# SmartSwitchV3.net
KiCad netlist of a schematic drawn in Altium Designer
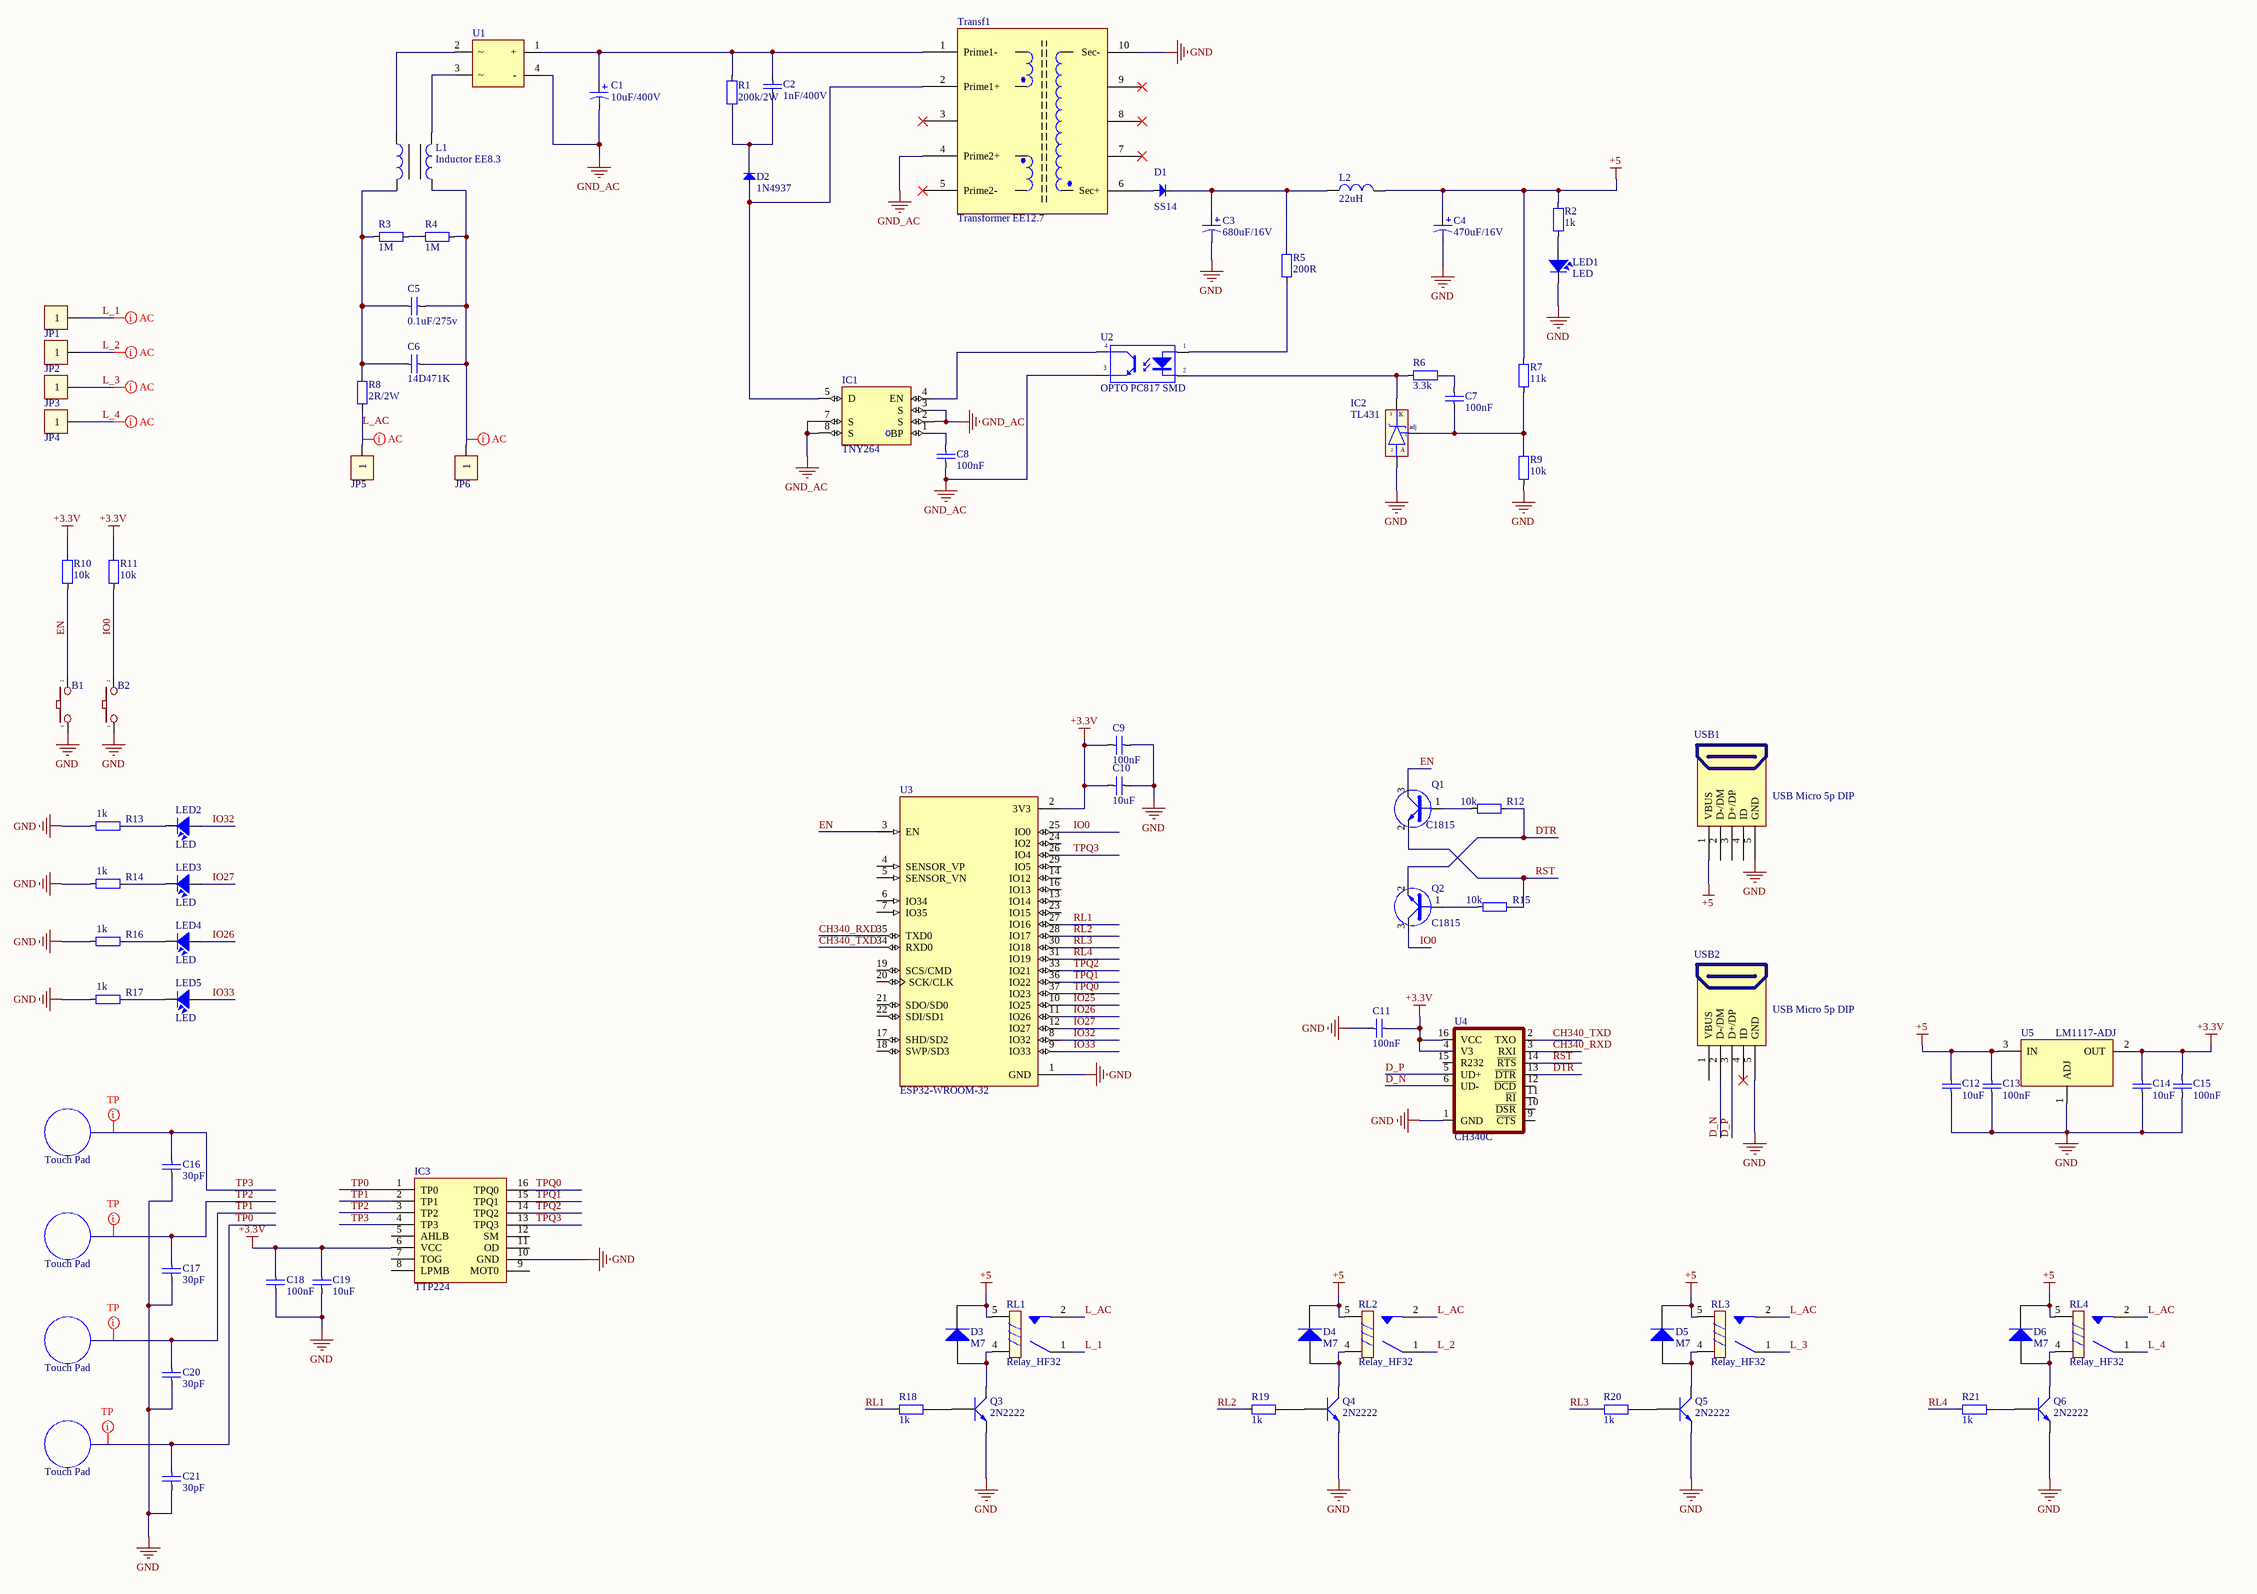
[diagram p0: SmartSwitchV3.SchDoc]

(export (version "E")
  (design (tool "Eeschema 10.0.6"))
  (components
    (comp (ref "B1")
      (value "Button 3x4x2.5")
      (footprint "Button 3x4x2.5")
      (libsource (lib "My Library") (part "Button 3x4x2.5"))
    )
    (comp (ref "B2")
      (value "Button 3x4x2.5")
      (footprint "Button 3x4x2.5")
      (libsource (lib "My Library") (part "Button 3x4x2.5"))
    )
    (comp (ref "C1")
      (value "10uF/400V")
      (footprint "C10mm")
      (description "Polarized Capacitor (Axial)")
      (fields (field (name "PUBLISHER") "Altium Limited"))
      (libsource (lib "My Library") (part "Cap Pol"))
    )
    (comp (ref "C2")
      (value "1nF/400V")
      (footprint "103/2KV")
      (description "CAP CERAMIC")
      (fields (field (name "PUBLISHER") "Altium Limited"))
      (libsource (lib "My Library") (part "Cap2KV"))
    )
    (comp (ref "C3")
      (value "680uF/16V")
      (footprint "C8mm")
      (description "Polarized Capacitor (Axial)")
      (fields (field (name "PUBLISHER") "Altium Limited"))
      (libsource (lib "My Library") (part "Cap Pol"))
    )
    (comp (ref "C4")
      (value "470uF/16V")
      (footprint "C8mm")
      (description "Polarized Capacitor (Axial)")
      (fields (field (name "PUBLISHER") "Altium Limited"))
      (libsource (lib "My Library") (part "Cap Pol"))
    )
    (comp (ref "C5")
      (value "0.1uF/275v")
      (footprint "Cap AC filter")
      (description "Tụ lọc nguồn AC 0.1uf 275v 10mm")
      (libsource (lib "My Library") (part "Cap AC filter"))
    )
    (comp (ref "C6")
      (value "14D471K")
      (footprint "103/2KV")
      (description "Capacitor Ceramic 2KV")
      (fields (field (name "PUBLISHER") "Altium Limited"))
      (libsource (lib "My Library") (part "Cap2KV"))
    )
    (comp (ref "C7")
      (value "100nF")
      (footprint "CAP_0805")
      (description "Capacitor")
      (fields (field (name "PUBLISHER") "Altium Limited"))
      (libsource (lib "My Library") (part "CapSMD"))
    )
    (comp (ref "C8")
      (value "100nF")
      (footprint "CAP_0805")
      (description "Capacitor")
      (fields (field (name "PUBLISHER") "Altium Limited"))
      (libsource (lib "My Library") (part "CapSMD"))
    )
    (comp (ref "C9")
      (value "100nF")
      (footprint "CAP_0805")
      (description "Capacitor")
      (fields (field (name "PUBLISHER") "Altium Limited"))
      (libsource (lib "My Library") (part "CapSMD"))
    )
    (comp (ref "C10")
      (value "10uF")
      (footprint "CAP_0805")
      (description "Capacitor")
      (fields (field (name "PUBLISHER") "Altium Limited"))
      (libsource (lib "My Library") (part "CapSMD"))
    )
    (comp (ref "C11")
      (value "100nF")
      (footprint "CAP_0805")
      (description "Capacitor")
      (fields (field (name "PUBLISHER") "Altium Limited"))
      (libsource (lib "My Library") (part "CapSMD"))
    )
    (comp (ref "C12")
      (value "10uF")
      (footprint "CAP_0805")
      (description "Capacitor")
      (fields (field (name "PUBLISHER") "Altium Limited"))
      (libsource (lib "My Library") (part "CapSMD"))
    )
    (comp (ref "C13")
      (value "100nF")
      (footprint "CAP_0805")
      (description "Capacitor")
      (fields (field (name "PUBLISHER") "Altium Limited"))
      (libsource (lib "My Library") (part "CapSMD"))
    )
    (comp (ref "C14")
      (value "10uF")
      (footprint "CAP_0805")
      (description "Capacitor")
      (fields (field (name "PUBLISHER") "Altium Limited"))
      (libsource (lib "My Library") (part "CapSMD"))
    )
    (comp (ref "C15")
      (value "100nF")
      (footprint "CAP_0805")
      (description "Capacitor")
      (fields (field (name "PUBLISHER") "Altium Limited"))
      (libsource (lib "My Library") (part "CapSMD"))
    )
    (comp (ref "C16")
      (value "30pF")
      (footprint "CAP_0805")
      (description "Capacitor")
      (fields (field (name "PUBLISHER") "Altium Limited"))
      (libsource (lib "My Library") (part "CapSMD"))
    )
    (comp (ref "C17")
      (value "30pF")
      (footprint "CAP_0805")
      (description "Capacitor")
      (fields (field (name "PUBLISHER") "Altium Limited"))
      (libsource (lib "My Library") (part "CapSMD"))
    )
    (comp (ref "C18")
      (value "100nF")
      (footprint "CAP_0805")
      (description "Capacitor")
      (fields (field (name "PUBLISHER") "Altium Limited"))
      (libsource (lib "My Library") (part "CapSMD"))
    )
    (comp (ref "C19")
      (value "10uF")
      (footprint "CAP_0805")
      (description "Capacitor")
      (fields (field (name "PUBLISHER") "Altium Limited"))
      (libsource (lib "My Library") (part "CapSMD"))
    )
    (comp (ref "C20")
      (value "30pF")
      (footprint "CAP_0805")
      (description "Capacitor")
      (fields (field (name "PUBLISHER") "Altium Limited"))
      (libsource (lib "My Library") (part "CapSMD"))
    )
    (comp (ref "C21")
      (value "30pF")
      (footprint "CAP_0805")
      (description "Capacitor")
      (fields (field (name "PUBLISHER") "Altium Limited"))
      (libsource (lib "My Library") (part "CapSMD"))
    )
    (comp (ref "D1")
      (value "SS14")
      (footprint "DO-214AA(SMB)")
      (description "Diode Schottky\r\n1N5819")
      (fields (field (name "PUBLISHER") "Altium Limited"))
      (libsource (lib "My Library") (part "Diode SMD"))
    )
    (comp (ref "D2")
      (value "1N4937")
      (footprint "DIO-1AN")
      (description "Diode Schottky\r\n1N4937")
      (fields (field (name "PUBLISHER") "Altium Limited"))
      (libsource (lib "My Library") (part "Diode SMD"))
    )
    (comp (ref "D3")
      (value "M7")
      (footprint "DIODE SMA")
      (description "Dán")
      (libsource (lib "Altium_Lib_by_KhueNguyenCreator") (part "Diode M7 ( 4007 )"))
    )
    (comp (ref "D4")
      (value "M7")
      (footprint "DIODE SMA")
      (description "Dán")
      (libsource (lib "Altium_Lib_by_KhueNguyenCreator") (part "Diode M7 ( 4007 )"))
    )
    (comp (ref "D5")
      (value "M7")
      (footprint "DIODE SMA")
      (description "Dán")
      (libsource (lib "Altium_Lib_by_KhueNguyenCreator") (part "Diode M7 ( 4007 )"))
    )
    (comp (ref "D6")
      (value "M7")
      (footprint "DIODE SMA")
      (description "Dán")
      (libsource (lib "Altium_Lib_by_KhueNguyenCreator") (part "Diode M7 ( 4007 )"))
    )
    (comp (ref "IC1")
      (value "TNY264")
      (footprint "TNY264")
      (description "IC Power")
      (libsource (lib "My Library") (part "TNY264"))
    )
    (comp (ref "IC2")
      (value "TL431")
      (footprint "qto-92")
      (description "Programmable Shunt Regulator")
      (libsource (lib "My Library") (part "TL431"))
    )
    (comp (ref "IC3") (value "TTP224") (footprint "TTP224") (libsource (lib "My Library") (part "TTP224")))
    (comp (ref "JP1")
      (value "Coc_dong")
      (footprint "Coc_dong")
      (libsource (lib "My Library") (part "Coc_dong"))
    )
    (comp (ref "JP2")
      (value "Coc_dong")
      (footprint "Coc_dong")
      (libsource (lib "My Library") (part "Coc_dong"))
    )
    (comp (ref "JP3")
      (value "Coc_dong")
      (footprint "Coc_dong")
      (libsource (lib "My Library") (part "Coc_dong"))
    )
    (comp (ref "JP4")
      (value "Coc_dong")
      (footprint "Coc_dong")
      (libsource (lib "My Library") (part "Coc_dong"))
    )
    (comp (ref "JP5") (value "Coc_dong") (footprint "Coc_dong") (libsource (lib "") (part "Coc_dong_1")))
    (comp (ref "JP6") (value "Coc_dong") (footprint "Coc_dong") (libsource (lib "") (part "Coc_dong_1")))
    (comp (ref "L1")
      (value "Inductor EE8.3")
      (footprint "Inductor EE8.3")
      (libsource (lib "My Library") (part "Inductor EE8.3"))
    )
    (comp (ref "L2")
      (value "22uH")
      (footprint "L_SMD")
      (description "CD73R 22uH 1.23A 7345")
      (libsource (lib "My Library") (part "Inductor"))
    )
    (comp (ref "LED1")
      (value "LED")
      (footprint "LED-0805-Red")
      (description "LED Single colour Green and Red")
      (libsource (lib "My Library") (part "LED"))
    )
    (comp (ref "LED2")
      (value "LED")
      (footprint "LED-0805-Red")
      (description "LED Single colour Green and Red")
      (libsource (lib "My Library") (part "LED"))
    )
    (comp (ref "LED3")
      (value "LED")
      (footprint "LED-0805-Red")
      (description "LED Single colour Green and Red")
      (libsource (lib "My Library") (part "LED"))
    )
    (comp (ref "LED4")
      (value "LED")
      (footprint "LED-0805-Red")
      (description "LED Single colour Green and Red")
      (libsource (lib "My Library") (part "LED"))
    )
    (comp (ref "LED5")
      (value "LED")
      (footprint "LED-0805-Red")
      (description "LED Single colour Green and Red")
      (libsource (lib "My Library") (part "LED"))
    )
    (comp (ref "Q1")
      (value "C1815")
      (footprint "SOT23D")
      (description "NPN 600mW, ECB")
      (libsource (lib "") (part "2SC1815_1"))
    )
    (comp (ref "Q2")
      (value "C1815")
      (footprint "SOT23D")
      (description "NPN 600mW, ECB")
      (libsource (lib "My Library") (part "2SC1815"))
    )
    (comp (ref "Q3")
      (value "2N2222")
      (footprint "SOT23")
      (description "NPN transistor")
      (libsource (lib "Altium_Lib_by_KhueNguyenCreator") (part "C1815 HF SMD"))
    )
    (comp (ref "Q4")
      (value "2N2222")
      (footprint "SOT23")
      (description "NPN transistor")
      (libsource (lib "Altium_Lib_by_KhueNguyenCreator") (part "C1815 HF SMD"))
    )
    (comp (ref "Q5")
      (value "2N2222")
      (footprint "SOT23")
      (description "NPN transistor")
      (libsource (lib "Altium_Lib_by_KhueNguyenCreator") (part "C1815 HF SMD"))
    )
    (comp (ref "Q6")
      (value "2N2222")
      (footprint "SOT23")
      (description "NPN transistor")
      (libsource (lib "Altium_Lib_by_KhueNguyenCreator") (part "C1815 HF SMD"))
    )
    (comp (ref "R1")
      (value "200k/2W")
      (footprint "RES-1WW")
      (description "Resistor")
      (fields
        (field (name "MANUFACTURER") "Generic Components")
        (field (name "PUBLISHER") "Altium Hobart Technology Centre")
      )
      (libsource (lib "My Library") (part "Resistor - SMD"))
    )
    (comp (ref "R2")
      (value "1k")
      (footprint "RES-SMD-0805")
      (description "Resistor")
      (fields
        (field (name "MANUFACTURER") "Generic Components")
        (field (name "PUBLISHER") "Altium Hobart Technology Centre")
      )
      (libsource (lib "My Library") (part "Resistor - SMD"))
    )
    (comp (ref "R3")
      (value "1M")
      (footprint "RES-SMD-1206")
      (description "Resistor")
      (fields
        (field (name "MANUFACTURER") "Generic Components")
        (field (name "PUBLISHER") "Altium Hobart Technology Centre")
      )
      (libsource (lib "My Library") (part "Resistor - SMD"))
    )
    (comp (ref "R4")
      (value "1M")
      (footprint "RES-SMD-1206")
      (description "Resistor")
      (fields
        (field (name "MANUFACTURER") "Generic Components")
        (field (name "PUBLISHER") "Altium Hobart Technology Centre")
      )
      (libsource (lib "My Library") (part "Resistor - SMD"))
    )
    (comp (ref "R5")
      (value "200R")
      (footprint "RES-SMD-0805")
      (description "Resistor")
      (fields
        (field (name "MANUFACTURER") "Generic Components")
        (field (name "PUBLISHER") "Altium Hobart Technology Centre")
      )
      (libsource (lib "My Library") (part "Resistor - SMD"))
    )
    (comp (ref "R6")
      (value "3.3k")
      (footprint "RES-SMD-0805")
      (description "Resistor")
      (fields
        (field (name "MANUFACTURER") "Generic Components")
        (field (name "PUBLISHER") "Altium Hobart Technology Centre")
      )
      (libsource (lib "My Library") (part "Resistor - SMD"))
    )
    (comp (ref "R7")
      (value "11k")
      (footprint "RES-SMD-0805")
      (description "Resistor")
      (fields
        (field (name "MANUFACTURER") "Generic Components")
        (field (name "PUBLISHER") "Altium Hobart Technology Centre")
      )
      (libsource (lib "My Library") (part "Resistor - SMD"))
    )
    (comp (ref "R8")
      (value "2R/2W")
      (footprint "RES-1WW")
      (description "Resistor")
      (fields
        (field (name "MANUFACTURER") "Generic Components")
        (field (name "PUBLISHER") "Altium Hobart Technology Centre")
      )
      (libsource (lib "My Library") (part "Resistor - SMD"))
    )
    (comp (ref "R9")
      (value "10k")
      (footprint "RES-SMD-0805")
      (description "Resistor")
      (fields
        (field (name "MANUFACTURER") "Generic Components")
        (field (name "PUBLISHER") "Altium Hobart Technology Centre")
      )
      (libsource (lib "My Library") (part "Resistor - SMD"))
    )
    (comp (ref "R10")
      (value "10k")
      (footprint "RES-SMD-0805")
      (description "Resistor")
      (fields
        (field (name "MANUFACTURER") "Generic Components")
        (field (name "PUBLISHER") "Altium Hobart Technology Centre")
      )
      (libsource (lib "My Library") (part "Resistor - SMD"))
    )
    (comp (ref "R11")
      (value "10k")
      (footprint "RES-SMD-0805")
      (description "Resistor")
      (fields
        (field (name "MANUFACTURER") "Generic Components")
        (field (name "PUBLISHER") "Altium Hobart Technology Centre")
      )
      (libsource (lib "My Library") (part "Resistor - SMD"))
    )
    (comp (ref "R12")
      (value "10k")
      (footprint "RES-SMD-0805")
      (description "Resistor")
      (fields
        (field (name "MANUFACTURER") "Generic Components")
        (field (name "PUBLISHER") "Altium Hobart Technology Centre")
      )
      (libsource (lib "My Library") (part "Resistor - SMD"))
    )
    (comp (ref "R13")
      (value "1k")
      (footprint "RES-SMD-0805")
      (description "Resistor")
      (fields
        (field (name "MANUFACTURER") "Generic Components")
        (field (name "PUBLISHER") "Altium Hobart Technology Centre")
      )
      (libsource (lib "My Library") (part "Resistor - SMD"))
    )
    (comp (ref "R14")
      (value "1k")
      (footprint "RES-SMD-0805")
      (description "Resistor")
      (fields
        (field (name "MANUFACTURER") "Generic Components")
        (field (name "PUBLISHER") "Altium Hobart Technology Centre")
      )
      (libsource (lib "My Library") (part "Resistor - SMD"))
    )
    (comp (ref "R15")
      (value "10k")
      (footprint "RES-SMD-0805")
      (description "Resistor")
      (fields
        (field (name "MANUFACTURER") "Generic Components")
        (field (name "PUBLISHER") "Altium Hobart Technology Centre")
      )
      (libsource (lib "My Library") (part "Resistor - SMD"))
    )
    (comp (ref "R16")
      (value "1k")
      (footprint "RES-SMD-0805")
      (description "Resistor")
      (fields
        (field (name "MANUFACTURER") "Generic Components")
        (field (name "PUBLISHER") "Altium Hobart Technology Centre")
      )
      (libsource (lib "My Library") (part "Resistor - SMD"))
    )
    (comp (ref "R17")
      (value "1k")
      (footprint "RES-SMD-0805")
      (description "Resistor")
      (fields
        (field (name "MANUFACTURER") "Generic Components")
        (field (name "PUBLISHER") "Altium Hobart Technology Centre")
      )
      (libsource (lib "My Library") (part "Resistor - SMD"))
    )
    (comp (ref "R18")
      (value "1k")
      (footprint "RES-SMD-0805")
      (description "Resistor")
      (fields
        (field (name "MANUFACTURER") "Generic Components")
        (field (name "PUBLISHER") "Altium Hobart Technology Centre")
      )
      (libsource (lib "My Library") (part "Resistor - SMD"))
    )
    (comp (ref "R19")
      (value "1k")
      (footprint "RES-SMD-0805")
      (description "Resistor")
      (fields
        (field (name "MANUFACTURER") "Generic Components")
        (field (name "PUBLISHER") "Altium Hobart Technology Centre")
      )
      (libsource (lib "My Library") (part "Resistor - SMD"))
    )
    (comp (ref "R20")
      (value "1k")
      (footprint "RES-SMD-0805")
      (description "Resistor")
      (fields
        (field (name "MANUFACTURER") "Generic Components")
        (field (name "PUBLISHER") "Altium Hobart Technology Centre")
      )
      (libsource (lib "My Library") (part "Resistor - SMD"))
    )
    (comp (ref "R21")
      (value "1k")
      (footprint "RES-SMD-0805")
      (description "Resistor")
      (fields
        (field (name "MANUFACTURER") "Generic Components")
        (field (name "PUBLISHER") "Altium Hobart Technology Centre")
      )
      (libsource (lib "My Library") (part "Resistor - SMD"))
    )
    (comp (ref "RL1")
      (value "Relay_HF32")
      (footprint "HF32F")
      (libsource (lib "My Library") (part "Relay_HF32"))
    )
    (comp (ref "RL2")
      (value "Relay_HF32")
      (footprint "HF32F")
      (libsource (lib "My Library") (part "Relay_HF32"))
    )
    (comp (ref "RL3")
      (value "Relay_HF32")
      (footprint "HF32F")
      (libsource (lib "My Library") (part "Relay_HF32"))
    )
    (comp (ref "RL4")
      (value "Relay_HF32")
      (footprint "HF32F")
      (libsource (lib "My Library") (part "Relay_HF32"))
    )
    (comp (ref "Transf1")
      (value "Transformer EE12.7")
      (footprint "Transformer EE12.7")
      (libsource (lib "My Library") (part "Tranformer EE16"))
    )
    (comp (ref "U1")
      (value "Diode Bridge Flate")
      (footprint "DB207S")
      (description "Diode Bridge")
      (libsource (lib "My Library") (part "Diode Bridge Flate"))
    )
    (comp (ref "U2")
      (value "OPTO PC817 SMD")
      (footprint "SOP4")
      (description "Single Opto")
      (libsource (lib "Altium_Lib_by_KhueNguyenCreator") (part "OPTO PC817 SMD"))
    )
    (comp (ref "U3")
      (value "ESP32-WROOM-32")
      (footprint "MODULE_ESP32-WROOM-32")
      (description "Bluetooth, WiFi Transceiver Module 2.4GHz ~ 2.5GHz Surface Mount")
      (fields (field (name "MF") "Espressif Systems") (field (name "DIGI-KEY_PART_NUMBER") "1904-1010-1-ND"))
      (libsource (lib "My Library") (part "ESP32-WROOM-32"))
    )
    (comp (ref "U4")
      (value "CH340C")
      (footprint "SO016")
      (description "USB to serial chip CH340")
      (fields (field (name "MF") "WCH"))
      (libsource (lib "My Library") (part "CH340C"))
    )
    (comp (ref "U5")
      (value "LM1117-ADJ")
      (footprint "LM1117-SOP")
      (description "800mA Low-Dropout Linear Regulator")
      (fields (field (name "CREATOR") "Nguyen Ba Bien"))
      (libsource (lib "My Library") (part "LM1117-ADJ"))
    )
    (comp (ref "USB1")
      (value "USB Micro 5p DIP")
      (footprint "USB Micro 5p DIP")
      (description "USB Type B")
      (libsource (lib "Altium_Lib_by_KhueNguyenCreator") (part "USB Micro 5p DIP"))
    )
    (comp (ref "USB2")
      (value "USB Micro 5p DIP")
      (footprint "USB Micro 5p DIP")
      (description "USB Type B")
      (libsource (lib "Altium_Lib_by_KhueNguyenCreator") (part "USB Micro 5p DIP"))
    )
  )
  (nets
    (net (code "1") (name "+3.3V") (class "Default")
      (node (ref "C10") (pin "1") (pinfunction "1_1") (pintype "passive"))
      (node (ref "C11") (pin "1") (pinfunction "1_1") (pintype "passive"))
      (node (ref "C14") (pin "1") (pinfunction "1_1") (pintype "passive"))
      (node (ref "C15") (pin "1") (pinfunction "1_1") (pintype "passive"))
      (node (ref "C18") (pin "2") (pinfunction "2_2") (pintype "passive"))
      (node (ref "C19") (pin "2") (pinfunction "2_2") (pintype "passive"))
      (node (ref "C9") (pin "1") (pinfunction "1_1") (pintype "passive"))
      (node (ref "IC3") (pin "6") (pinfunction "VCC_6") (pintype "passive"))
      (node (ref "R10") (pin "1") (pinfunction "1_1") (pintype "passive"))
      (node (ref "R11") (pin "1") (pinfunction "1_1") (pintype "passive"))
      (node (ref "U3") (pin "2") (pinfunction "3V3_2") (pintype "power_in"))
      (node (ref "U4") (pin "16") (pinfunction "VCC_16") (pintype "bidirectional"))
      (node (ref "U4") (pin "4") (pinfunction "V3_4") (pintype "bidirectional"))
      (node (ref "U5") (pin "2") (pinfunction "OUT_2") (pintype "passive"))
    )
    (net (code "2") (name "+5") (class "Default")
      (node (ref "C12") (pin "1") (pinfunction "1_1") (pintype "passive"))
      (node (ref "C13") (pin "1") (pinfunction "1_1") (pintype "passive"))
      (node (ref "C4") (pin "1") (pinfunction "1_1") (pintype "passive"))
      (node (ref "D3") (pin "2") (pinfunction "K_2") (pintype "passive"))
      (node (ref "D4") (pin "2") (pinfunction "K_2") (pintype "passive"))
      (node (ref "D5") (pin "2") (pinfunction "K_2") (pintype "passive"))
      (node (ref "D6") (pin "2") (pinfunction "K_2") (pintype "passive"))
      (node (ref "L2") (pin "2") (pinfunction "2_2") (pintype "passive"))
      (node (ref "R2") (pin "2") (pinfunction "2_2") (pintype "passive"))
      (node (ref "R7") (pin "2") (pinfunction "2_2") (pintype "passive"))
      (node (ref "RL1") (pin "5") (pinfunction "5_5") (pintype "passive"))
      (node (ref "RL2") (pin "5") (pinfunction "5_5") (pintype "passive"))
      (node (ref "RL3") (pin "5") (pinfunction "5_5") (pintype "passive"))
      (node (ref "RL4") (pin "5") (pinfunction "5_5") (pintype "passive"))
      (node (ref "U5") (pin "3") (pinfunction "IN_3") (pintype "passive"))
      (node (ref "USB1") (pin "1") (pinfunction "VBUS_1") (pintype "passive"))
    )
    (net (code "3") (name "/CH340_RXD") (class "Default")
      (node (ref "U3") (pin "35") (pinfunction "TXD0_35") (pintype "bidirectional"))
      (node (ref "U4") (pin "3") (pinfunction "RXI_3") (pintype "bidirectional"))
    )
    (net (code "4") (name "/CH340_TXD") (class "Default")
      (node (ref "U3") (pin "34") (pinfunction "RXD0_34") (pintype "bidirectional"))
      (node (ref "U4") (pin "2") (pinfunction "TXO_2") (pintype "bidirectional"))
    )
    (net (code "5") (name "/DTR") (class "Default")
      (node (ref "Q2") (pin "2") (pinfunction "E_2") (pintype "passive"))
      (node (ref "R12") (pin "1") (pinfunction "1_1") (pintype "passive"))
      (node (ref "U4") (pin "13") (pinfunction "~{DTR}_13") (pintype "bidirectional"))
    )
    (net (code "6") (name "/D_N") (class "Default")
      (node (ref "U4") (pin "6") (pinfunction "UD-_6") (pintype "bidirectional"))
      (node (ref "USB2") (pin "2") (pinfunction "D-/DM_2") (pintype "passive"))
    )
    (net (code "7") (name "/D_P") (class "Default")
      (node (ref "U4") (pin "5") (pinfunction "UD+_5") (pintype "bidirectional"))
      (node (ref "USB2") (pin "3") (pinfunction "D+/DP_3") (pintype "passive"))
    )
    (net (code "8") (name "/EN") (class "Default")
      (node (ref "B1") (pin "2") (pinfunction "2_2") (pintype "passive"))
      (node (ref "Q1") (pin "3") (pinfunction "C_3") (pintype "passive"))
      (node (ref "R10") (pin "2") (pinfunction "2_2") (pintype "passive"))
      (node (ref "U3") (pin "3") (pinfunction "EN_3") (pintype "input"))
    )
    (net (code "9") (name "/IO0") (class "Default")
      (node (ref "B2") (pin "2") (pinfunction "2_2") (pintype "passive"))
      (node (ref "Q2") (pin "3") (pinfunction "C_3") (pintype "passive"))
      (node (ref "R11") (pin "2") (pinfunction "2_2") (pintype "passive"))
      (node (ref "U3") (pin "25") (pinfunction "IO0_25") (pintype "bidirectional"))
    )
    (net (code "10") (name "/IO25") (class "Default")
      (node (ref "U3") (pin "10") (pinfunction "IO25_10") (pintype "bidirectional"))
    )
    (net (code "11") (name "/IO26") (class "Default")
      (node (ref "LED4") (pin "1") (pinfunction "1_1") (pintype "passive"))
      (node (ref "U3") (pin "11") (pinfunction "IO26_11") (pintype "bidirectional"))
    )
    (net (code "12") (name "/IO27") (class "Default")
      (node (ref "LED3") (pin "1") (pinfunction "1_1") (pintype "passive"))
      (node (ref "U3") (pin "12") (pinfunction "IO27_12") (pintype "bidirectional"))
    )
    (net (code "13") (name "/IO32") (class "Default")
      (node (ref "LED2") (pin "1") (pinfunction "1_1") (pintype "passive"))
      (node (ref "U3") (pin "8") (pinfunction "IO32_8") (pintype "bidirectional"))
    )
    (net (code "14") (name "/IO33") (class "Default")
      (node (ref "LED5") (pin "1") (pinfunction "1_1") (pintype "passive"))
      (node (ref "U3") (pin "9") (pinfunction "IO33_9") (pintype "bidirectional"))
    )
    (net (code "15") (name "/L_1") (class "Default")
      (node (ref "JP1") (pin "1") (pinfunction "1_1") (pintype "passive"))
      (node (ref "RL1") (pin "1") (pinfunction "1_1") (pintype "passive"))
    )
    (net (code "16") (name "/L_2") (class "Default")
      (node (ref "JP2") (pin "1") (pinfunction "1_1") (pintype "passive"))
      (node (ref "RL2") (pin "1") (pinfunction "1_1") (pintype "passive"))
    )
    (net (code "17") (name "/L_3") (class "Default")
      (node (ref "JP3") (pin "1") (pinfunction "1_1") (pintype "passive"))
      (node (ref "RL3") (pin "1") (pinfunction "1_1") (pintype "passive"))
    )
    (net (code "18") (name "/L_4") (class "Default")
      (node (ref "JP4") (pin "1") (pinfunction "1_1") (pintype "passive"))
      (node (ref "RL4") (pin "1") (pinfunction "1_1") (pintype "passive"))
    )
    (net (code "19") (name "/L_AC") (class "Default")
      (node (ref "JP5") (pin "1") (pinfunction "1_1") (pintype "passive"))
      (node (ref "R8") (pin "1") (pinfunction "1_1") (pintype "passive"))
      (node (ref "RL1") (pin "2") (pinfunction "2_2") (pintype "passive"))
      (node (ref "RL2") (pin "2") (pinfunction "2_2") (pintype "passive"))
      (node (ref "RL3") (pin "2") (pinfunction "2_2") (pintype "passive"))
      (node (ref "RL4") (pin "2") (pinfunction "2_2") (pintype "passive"))
    )
    (net (code "20") (name "/RL1") (class "Default")
      (node (ref "R18") (pin "1") (pinfunction "1_1") (pintype "passive"))
      (node (ref "U3") (pin "27") (pinfunction "IO16_27") (pintype "bidirectional"))
    )
    (net (code "21") (name "/RL2") (class "Default")
      (node (ref "R19") (pin "1") (pinfunction "1_1") (pintype "passive"))
      (node (ref "U3") (pin "28") (pinfunction "IO17_28") (pintype "bidirectional"))
    )
    (net (code "22") (name "/RL3") (class "Default")
      (node (ref "R20") (pin "1") (pinfunction "1_1") (pintype "passive"))
      (node (ref "U3") (pin "30") (pinfunction "IO18_30") (pintype "bidirectional"))
    )
    (net (code "23") (name "/RL4") (class "Default")
      (node (ref "R21") (pin "1") (pinfunction "1_1") (pintype "passive"))
      (node (ref "U3") (pin "31") (pinfunction "IO19_31") (pintype "bidirectional"))
    )
    (net (code "24") (name "/RST") (class "Default")
      (node (ref "Q1") (pin "2") (pinfunction "E_2") (pintype "passive"))
      (node (ref "R15") (pin "1") (pinfunction "1_1") (pintype "passive"))
      (node (ref "U4") (pin "14") (pinfunction "~{RTS}_14") (pintype "bidirectional"))
    )
    (net (code "25") (name "/TP0") (class "Default")
      (node (ref "C21") (pin "2") (pinfunction "2_2") (pintype "passive"))
      (node (ref "IC3") (pin "1") (pinfunction "TP0_1") (pintype "passive"))
    )
    (net (code "26") (name "/TP1") (class "Default")
      (node (ref "C20") (pin "2") (pinfunction "2_2") (pintype "passive"))
      (node (ref "IC3") (pin "2") (pinfunction "TP1_2") (pintype "passive"))
    )
    (net (code "27") (name "/TP2") (class "Default")
      (node (ref "C17") (pin "2") (pinfunction "2_2") (pintype "passive"))
      (node (ref "IC3") (pin "3") (pinfunction "TP2_3") (pintype "passive"))
    )
    (net (code "28") (name "/TP3") (class "Default")
      (node (ref "C16") (pin "2") (pinfunction "2_2") (pintype "passive"))
      (node (ref "IC3") (pin "4") (pinfunction "TP3_4") (pintype "passive"))
    )
    (net (code "29") (name "/TPQ0") (class "Default")
      (node (ref "IC3") (pin "16") (pinfunction "TPQ0_16") (pintype "passive"))
      (node (ref "U3") (pin "37") (pinfunction "IO23_37") (pintype "bidirectional"))
    )
    (net (code "30") (name "/TPQ1") (class "Default")
      (node (ref "IC3") (pin "15") (pinfunction "TPQ1_15") (pintype "passive"))
      (node (ref "U3") (pin "36") (pinfunction "IO22_36") (pintype "bidirectional"))
    )
    (net (code "31") (name "/TPQ2") (class "Default")
      (node (ref "IC3") (pin "14") (pinfunction "TPQ2_14") (pintype "passive"))
      (node (ref "U3") (pin "33") (pinfunction "IO21_33") (pintype "bidirectional"))
    )
    (net (code "32") (name "/TPQ3") (class "Default")
      (node (ref "IC3") (pin "13") (pinfunction "TPQ3_13") (pintype "passive"))
      (node (ref "U3") (pin "26") (pinfunction "IO4_26") (pintype "bidirectional"))
    )
    (net (code "33") (name "GND") (class "Default")
      (node (ref "B1") (pin "1") (pinfunction "1_1") (pintype "passive"))
      (node (ref "B2") (pin "1") (pinfunction "1_1") (pintype "passive"))
      (node (ref "C10") (pin "2") (pinfunction "2_2") (pintype "passive"))
      (node (ref "C11") (pin "2") (pinfunction "2_2") (pintype "passive"))
      (node (ref "C12") (pin "2") (pinfunction "2_2") (pintype "passive"))
      (node (ref "C13") (pin "2") (pinfunction "2_2") (pintype "passive"))
      (node (ref "C14") (pin "2") (pinfunction "2_2") (pintype "passive"))
      (node (ref "C15") (pin "2") (pinfunction "2_2") (pintype "passive"))
      (node (ref "C16") (pin "1") (pinfunction "1_1") (pintype "passive"))
      (node (ref "C17") (pin "1") (pinfunction "1_1") (pintype "passive"))
      (node (ref "C18") (pin "1") (pinfunction "1_1") (pintype "passive"))
      (node (ref "C19") (pin "1") (pinfunction "1_1") (pintype "passive"))
      (node (ref "C20") (pin "1") (pinfunction "1_1") (pintype "passive"))
      (node (ref "C21") (pin "1") (pinfunction "1_1") (pintype "passive"))
      (node (ref "C3") (pin "2") (pinfunction "2_2") (pintype "passive"))
      (node (ref "C4") (pin "2") (pinfunction "2_2") (pintype "passive"))
      (node (ref "C9") (pin "2") (pinfunction "2_2") (pintype "passive"))
      (node (ref "IC2") (pin "2") (pinfunction "A_2") (pintype "passive"))
      (node (ref "IC3") (pin "10") (pinfunction "GND_10") (pintype "passive"))
      (node (ref "LED1") (pin "2") (pinfunction "2_2") (pintype "passive"))
      (node (ref "Q3") (pin "2") (pinfunction "E_2") (pintype "passive"))
      (node (ref "Q4") (pin "2") (pinfunction "E_2") (pintype "passive"))
      (node (ref "Q5") (pin "2") (pinfunction "E_2") (pintype "passive"))
      (node (ref "Q6") (pin "2") (pinfunction "E_2") (pintype "passive"))
      (node (ref "R13") (pin "2") (pinfunction "2_2") (pintype "passive"))
      (node (ref "R14") (pin "2") (pinfunction "2_2") (pintype "passive"))
      (node (ref "R16") (pin "2") (pinfunction "2_2") (pintype "passive"))
      (node (ref "R17") (pin "2") (pinfunction "2_2") (pintype "passive"))
      (node (ref "R9") (pin "1") (pinfunction "1_1") (pintype "passive"))
      (node (ref "Transf1") (pin "10") (pinfunction "Sec-_10") (pintype "passive"))
      (node (ref "U3") (pin "1") (pinfunction "GND_1") (pintype "power_in"))
      (node (ref "U4") (pin "1") (pinfunction "GND_1") (pintype "bidirectional"))
      (node (ref "U5") (pin "1") (pinfunction "ADJ_1") (pintype "passive"))
      (node (ref "USB1") (pin "5") (pinfunction "GND_5") (pintype "passive"))
      (node (ref "USB2") (pin "5") (pinfunction "GND_5") (pintype "passive"))
    )
    (net (code "34") (name "GND_AC") (class "Default")
      (node (ref "C1") (pin "2") (pinfunction "2_2") (pintype "passive"))
      (node (ref "C8") (pin "1") (pinfunction "1_1") (pintype "passive"))
      (node (ref "IC1") (pin "2") (pinfunction "S_2") (pintype "bidirectional"))
      (node (ref "IC1") (pin "3") (pinfunction "S_3") (pintype "bidirectional"))
      (node (ref "IC1") (pin "7") (pinfunction "S_7") (pintype "bidirectional"))
      (node (ref "IC1") (pin "8") (pinfunction "S_8") (pintype "bidirectional"))
      (node (ref "Transf1") (pin "4") (pinfunction "Prime2+_4") (pintype "passive"))
      (node (ref "U1") (pin "4") (pinfunction "-_4") (pintype "passive"))
      (node (ref "U2") (pin "3") (pinfunction "E_3") (pintype "passive"))
    )
    (net (code "35") (name "Net-(C5-Pad1)") (class "Default")
      (node (ref "C5") (pin "1") (pinfunction "1_1") (pintype "passive"))
      (node (ref "C6") (pin "1") (pinfunction "1_1") (pintype "passive"))
      (node (ref "JP6") (pin "1") (pinfunction "1_1") (pintype "passive"))
      (node (ref "L1") (pin "4") (pinfunction "4_4") (pintype "passive"))
      (node (ref "R4") (pin "1") (pinfunction "1_1") (pintype "passive"))
    )
    (net (code "36") (name "Net-(C5-Pad2)") (class "Default")
      (node (ref "C5") (pin "2") (pinfunction "2_2") (pintype "passive"))
      (node (ref "C6") (pin "2") (pinfunction "2_2") (pintype "passive"))
      (node (ref "L1") (pin "2") (pinfunction "2_2") (pintype "passive"))
      (node (ref "R3") (pin "2") (pinfunction "2_2") (pintype "passive"))
      (node (ref "R8") (pin "2") (pinfunction "2_2") (pintype "passive"))
    )
    (net (code "37") (name "Net-(C7-Pad2)") (class "Default")
      (node (ref "C7") (pin "2") (pinfunction "2_2") (pintype "passive"))
      (node (ref "R6") (pin "1") (pinfunction "1_1") (pintype "passive"))
    )
    (net (code "38") (name "Net-(D1-A)") (class "Default")
      (node (ref "D1") (pin "1") (pinfunction "A_1") (pintype "passive"))
      (node (ref "Transf1") (pin "6") (pinfunction "Sec+_6") (pintype "passive"))
    )
    (net (code "39") (name "Net-(D1-K)") (class "Default")
      (node (ref "C3") (pin "1") (pinfunction "1_1") (pintype "passive"))
      (node (ref "D1") (pin "2") (pinfunction "K_2") (pintype "passive"))
      (node (ref "L2") (pin "1") (pinfunction "1_1") (pintype "passive"))
      (node (ref "R5") (pin "2") (pinfunction "2_2") (pintype "passive"))
    )
    (net (code "40") (name "Net-(D2-A)") (class "Default")
      (node (ref "D2") (pin "1") (pinfunction "A_1") (pintype "passive"))
      (node (ref "IC1") (pin "5") (pinfunction "D_5") (pintype "bidirectional"))
      (node (ref "Transf1") (pin "2") (pinfunction "Prime1+_2") (pintype "passive"))
    )
    (net (code "41") (name "Net-(D2-K)") (class "Default")
      (node (ref "C2") (pin "2") (pinfunction "2_2") (pintype "passive"))
      (node (ref "D2") (pin "2") (pinfunction "K_2") (pintype "passive"))
      (node (ref "R1") (pin "1") (pinfunction "1_1") (pintype "passive"))
    )
    (net (code "42") (name "Net-(D3-A)") (class "Default")
      (node (ref "D3") (pin "1") (pinfunction "A_1") (pintype "passive"))
      (node (ref "Q3") (pin "3") (pinfunction "C_3") (pintype "passive"))
      (node (ref "RL1") (pin "4") (pinfunction "4_4") (pintype "passive"))
    )
    (net (code "43") (name "Net-(D4-A)") (class "Default")
      (node (ref "D4") (pin "1") (pinfunction "A_1") (pintype "passive"))
      (node (ref "Q4") (pin "3") (pinfunction "C_3") (pintype "passive"))
      (node (ref "RL2") (pin "4") (pinfunction "4_4") (pintype "passive"))
    )
    (net (code "44") (name "Net-(D5-A)") (class "Default")
      (node (ref "D5") (pin "1") (pinfunction "A_1") (pintype "passive"))
      (node (ref "Q5") (pin "3") (pinfunction "C_3") (pintype "passive"))
      (node (ref "RL3") (pin "4") (pinfunction "4_4") (pintype "passive"))
    )
    (net (code "45") (name "Net-(D6-A)") (class "Default")
      (node (ref "D6") (pin "1") (pinfunction "A_1") (pintype "passive"))
      (node (ref "Q6") (pin "3") (pinfunction "C_3") (pintype "passive"))
      (node (ref "RL4") (pin "4") (pinfunction "4_4") (pintype "passive"))
    )
    (net (code "46") (name "Net-(IC1-BP)") (class "Default")
      (node (ref "C8") (pin "2") (pinfunction "2_2") (pintype "passive"))
      (node (ref "IC1") (pin "1") (pinfunction "BP_1") (pintype "bidirectional"))
    )
    (net (code "47") (name "Net-(IC1-EN)") (class "Default")
      (node (ref "IC1") (pin "4") (pinfunction "EN_4") (pintype "bidirectional"))
      (node (ref "U2") (pin "4") (pinfunction "C_4") (pintype "passive"))
    )
    (net (code "48") (name "Net-(IC2-K)") (class "Default")
      (node (ref "IC2") (pin "3") (pinfunction "K_3") (pintype "passive"))
      (node (ref "R6") (pin "2") (pinfunction "2_2") (pintype "passive"))
      (node (ref "U2") (pin "2") (pinfunction "K_2") (pintype "passive"))
    )
    (net (code "49") (name "Net-(IC2-adj)") (class "Default")
      (node (ref "C7") (pin "1") (pinfunction "1_1") (pintype "passive"))
      (node (ref "IC2") (pin "1") (pinfunction "adj_1") (pintype "passive"))
      (node (ref "R7") (pin "1") (pinfunction "1_1") (pintype "passive"))
      (node (ref "R9") (pin "2") (pinfunction "2_2") (pintype "passive"))
    )
    (net (code "50") (name "Net-(L1-Pad1)") (class "Default")
      (node (ref "L1") (pin "1") (pinfunction "1_1") (pintype "passive"))
      (node (ref "U1") (pin "2") (pinfunction "~_2") (pintype "passive"))
    )
    (net (code "51") (name "Net-(L1-Pad3)") (class "Default")
      (node (ref "L1") (pin "3") (pinfunction "3_3") (pintype "passive"))
      (node (ref "U1") (pin "3") (pinfunction "~_3") (pintype "passive"))
    )
    (net (code "52") (name "Net-(LED1-Pad1)") (class "Default")
      (node (ref "LED1") (pin "1") (pinfunction "1_1") (pintype "passive"))
      (node (ref "R2") (pin "1") (pinfunction "1_1") (pintype "passive"))
    )
    (net (code "53") (name "Net-(LED2-Pad2)") (class "Default")
      (node (ref "LED2") (pin "2") (pinfunction "2_2") (pintype "passive"))
      (node (ref "R13") (pin "1") (pinfunction "1_1") (pintype "passive"))
    )
    (net (code "54") (name "Net-(LED3-Pad2)") (class "Default")
      (node (ref "LED3") (pin "2") (pinfunction "2_2") (pintype "passive"))
      (node (ref "R14") (pin "1") (pinfunction "1_1") (pintype "passive"))
    )
    (net (code "55") (name "Net-(LED4-Pad2)") (class "Default")
      (node (ref "LED4") (pin "2") (pinfunction "2_2") (pintype "passive"))
      (node (ref "R16") (pin "1") (pinfunction "1_1") (pintype "passive"))
    )
    (net (code "56") (name "Net-(LED5-Pad2)") (class "Default")
      (node (ref "LED5") (pin "2") (pinfunction "2_2") (pintype "passive"))
      (node (ref "R17") (pin "1") (pinfunction "1_1") (pintype "passive"))
    )
    (net (code "57") (name "Net-(Q1-B)") (class "Default")
      (node (ref "Q1") (pin "1") (pinfunction "B_1") (pintype "passive"))
      (node (ref "R12") (pin "2") (pinfunction "2_2") (pintype "passive"))
    )
    (net (code "58") (name "Net-(Q2-B)") (class "Default")
      (node (ref "Q2") (pin "1") (pinfunction "B_1") (pintype "passive"))
      (node (ref "R15") (pin "2") (pinfunction "2_2") (pintype "passive"))
    )
    (net (code "59") (name "Net-(Q3-B)") (class "Default")
      (node (ref "Q3") (pin "1") (pinfunction "B_1") (pintype "passive"))
      (node (ref "R18") (pin "2") (pinfunction "2_2") (pintype "passive"))
    )
    (net (code "60") (name "Net-(Q4-B)") (class "Default")
      (node (ref "Q4") (pin "1") (pinfunction "B_1") (pintype "passive"))
      (node (ref "R19") (pin "2") (pinfunction "2_2") (pintype "passive"))
    )
    (net (code "61") (name "Net-(Q5-B)") (class "Default")
      (node (ref "Q5") (pin "1") (pinfunction "B_1") (pintype "passive"))
      (node (ref "R20") (pin "2") (pinfunction "2_2") (pintype "passive"))
    )
    (net (code "62") (name "Net-(Q6-B)") (class "Default")
      (node (ref "Q6") (pin "1") (pinfunction "B_1") (pintype "passive"))
      (node (ref "R21") (pin "2") (pinfunction "2_2") (pintype "passive"))
    )
    (net (code "63") (name "Net-(R3-Pad1)") (class "Default")
      (node (ref "R3") (pin "1") (pinfunction "1_1") (pintype "passive"))
      (node (ref "R4") (pin "2") (pinfunction "2_2") (pintype "passive"))
    )
    (net (code "64") (name "Net-(Transf1-Prime1-)") (class "Default")
      (node (ref "C1") (pin "1") (pinfunction "1_1") (pintype "passive"))
      (node (ref "C2") (pin "1") (pinfunction "1_1") (pintype "passive"))
      (node (ref "R1") (pin "2") (pinfunction "2_2") (pintype "passive"))
      (node (ref "Transf1") (pin "1") (pinfunction "Prime1-_1") (pintype "passive"))
      (node (ref "U1") (pin "1") (pinfunction "+_1") (pintype "passive"))
    )
    (net (code "65") (name "Net-(U2-A)") (class "Default")
      (node (ref "R5") (pin "1") (pinfunction "1_1") (pintype "passive"))
      (node (ref "U2") (pin "1") (pinfunction "A_1") (pintype "passive"))
    )
    (net (code "66") (name "unconnected-(IC3-AHLB-Pad5)") (class "Default")
      (node (ref "IC3") (pin "5") (pinfunction "AHLB_5") (pintype "passive"))
    )
    (net (code "67") (name "unconnected-(IC3-LPMB-Pad8)") (class "Default")
      (node (ref "IC3") (pin "8") (pinfunction "LPMB_8") (pintype "passive"))
    )
    (net (code "68") (name "unconnected-(IC3-MOT0-Pad9)") (class "Default")
      (node (ref "IC3") (pin "9") (pinfunction "MOT0_9") (pintype "passive"))
    )
    (net (code "69") (name "unconnected-(IC3-OD-Pad11)") (class "Default")
      (node (ref "IC3") (pin "11") (pinfunction "OD_11") (pintype "passive"))
    )
    (net (code "70") (name "unconnected-(IC3-SM-Pad12)") (class "Default")
      (node (ref "IC3") (pin "12") (pinfunction "SM_12") (pintype "passive"))
    )
    (net (code "71") (name "unconnected-(IC3-TOG-Pad7)") (class "Default")
      (node (ref "IC3") (pin "7") (pinfunction "TOG_7") (pintype "passive"))
    )
    (net (code "72") (name "unconnected-(Transf1-Pad3)") (class "Default")
      (node (ref "Transf1") (pin "3") (pintype "passive+no_connect"))
    )
    (net (code "73") (name "unconnected-(Transf1-Pad7)") (class "Default")
      (node (ref "Transf1") (pin "7") (pintype "passive+no_connect"))
    )
    (net (code "74") (name "unconnected-(Transf1-Pad8)") (class "Default")
      (node (ref "Transf1") (pin "8") (pintype "passive+no_connect"))
    )
    (net (code "75") (name "unconnected-(Transf1-Pad9)") (class "Default")
      (node (ref "Transf1") (pin "9") (pintype "passive+no_connect"))
    )
    (net (code "76") (name "unconnected-(Transf1-Prime2--Pad5)") (class "Default")
      (node (ref "Transf1") (pin "5") (pinfunction "Prime2-_5") (pintype "passive+no_connect"))
    )
    (net (code "77") (name "unconnected-(U3-IO2-Pad24)") (class "Default")
      (node (ref "U3") (pin "24") (pinfunction "IO2_24") (pintype "bidirectional"))
    )
    (net (code "78") (name "unconnected-(U3-IO5-Pad29)") (class "Default")
      (node (ref "U3") (pin "29") (pinfunction "IO5_29") (pintype "bidirectional"))
    )
    (net (code "79") (name "unconnected-(U3-IO12-Pad14)") (class "Default")
      (node (ref "U3") (pin "14") (pinfunction "IO12_14") (pintype "bidirectional"))
    )
    (net (code "80") (name "unconnected-(U3-IO13-Pad16)") (class "Default")
      (node (ref "U3") (pin "16") (pinfunction "IO13_16") (pintype "bidirectional"))
    )
    (net (code "81") (name "unconnected-(U3-IO14-Pad13)") (class "Default")
      (node (ref "U3") (pin "13") (pinfunction "IO14_13") (pintype "bidirectional"))
    )
    (net (code "82") (name "unconnected-(U3-IO15-Pad23)") (class "Default")
      (node (ref "U3") (pin "23") (pinfunction "IO15_23") (pintype "bidirectional"))
    )
    (net (code "83") (name "unconnected-(U3-IO34-Pad6)") (class "Default")
      (node (ref "U3") (pin "6") (pinfunction "IO34_6") (pintype "input"))
    )
    (net (code "84") (name "unconnected-(U3-IO35-Pad7)") (class "Default")
      (node (ref "U3") (pin "7") (pinfunction "IO35_7") (pintype "input"))
    )
    (net (code "85") (name "unconnected-(U3-SCK{slash}CLK-Pad20)") (class "Default")
      (node (ref "U3") (pin "20") (pinfunction "SCK/CLK_20") (pintype "bidirectional"))
    )
    (net (code "86") (name "unconnected-(U3-SCS{slash}CMD-Pad19)") (class "Default")
      (node (ref "U3") (pin "19") (pinfunction "SCS/CMD_19") (pintype "bidirectional"))
    )
    (net (code "87") (name "unconnected-(U3-SDI{slash}SD1-Pad22)") (class "Default")
      (node (ref "U3") (pin "22") (pinfunction "SDI/SD1_22") (pintype "bidirectional"))
    )
    (net (code "88") (name "unconnected-(U3-SDO{slash}SD0-Pad21)") (class "Default")
      (node (ref "U3") (pin "21") (pinfunction "SDO/SD0_21") (pintype "bidirectional"))
    )
    (net (code "89") (name "unconnected-(U3-SENSOR_VN-Pad5)") (class "Default")
      (node (ref "U3") (pin "5") (pinfunction "SENSOR_VN_5") (pintype "input"))
    )
    (net (code "90") (name "unconnected-(U3-SENSOR_VP-Pad4)") (class "Default")
      (node (ref "U3") (pin "4") (pinfunction "SENSOR_VP_4") (pintype "input"))
    )
    (net (code "91") (name "unconnected-(U3-SHD{slash}SD2-Pad17)") (class "Default")
      (node (ref "U3") (pin "17") (pinfunction "SHD/SD2_17") (pintype "bidirectional"))
    )
    (net (code "92") (name "unconnected-(U3-SWP{slash}SD3-Pad18)") (class "Default")
      (node (ref "U3") (pin "18") (pinfunction "SWP/SD3_18") (pintype "bidirectional"))
    )
    (net (code "93") (name "unconnected-(U4-R232-Pad15)") (class "Default")
      (node (ref "U4") (pin "15") (pinfunction "R232_15") (pintype "bidirectional"))
    )
    (net (code "94") (name "unconnected-(U4-~{CTS}-Pad9)") (class "Default")
      (node (ref "U4") (pin "9") (pinfunction "~{CTS}_9") (pintype "bidirectional"))
    )
    (net (code "95") (name "unconnected-(U4-~{DCD}-Pad12)") (class "Default")
      (node (ref "U4") (pin "12") (pinfunction "~{DCD}_12") (pintype "bidirectional"))
    )
    (net (code "96") (name "unconnected-(U4-~{DSR}-Pad10)") (class "Default")
      (node (ref "U4") (pin "10") (pinfunction "~{DSR}_10") (pintype "bidirectional"))
    )
    (net (code "97") (name "unconnected-(U4-~{RI}-Pad11)") (class "Default")
      (node (ref "U4") (pin "11") (pinfunction "~{RI}_11") (pintype "bidirectional"))
    )
    (net (code "98") (name "unconnected-(USB1-D+{slash}DP-Pad3)") (class "Default")
      (node (ref "USB1") (pin "3") (pinfunction "D+/DP_3") (pintype "passive"))
    )
    (net (code "99") (name "unconnected-(USB1-D-{slash}DM-Pad2)") (class "Default")
      (node (ref "USB1") (pin "2") (pinfunction "D-/DM_2") (pintype "passive"))
    )
    (net (code "100") (name "unconnected-(USB1-ID-Pad4)") (class "Default")
      (node (ref "USB1") (pin "4") (pinfunction "ID_4") (pintype "passive"))
    )
    (net (code "101") (name "unconnected-(USB2-ID-Pad4)") (class "Default")
      (node (ref "USB2") (pin "4") (pinfunction "ID_4") (pintype "passive+no_connect"))
    )
    (net (code "102") (name "unconnected-(USB2-VBUS-Pad1)") (class "Default")
      (node (ref "USB2") (pin "1") (pinfunction "VBUS_1") (pintype "passive"))
    )
  )
)
